# product_038.net
KiCad netlist of a schematic drawn in EAGLE
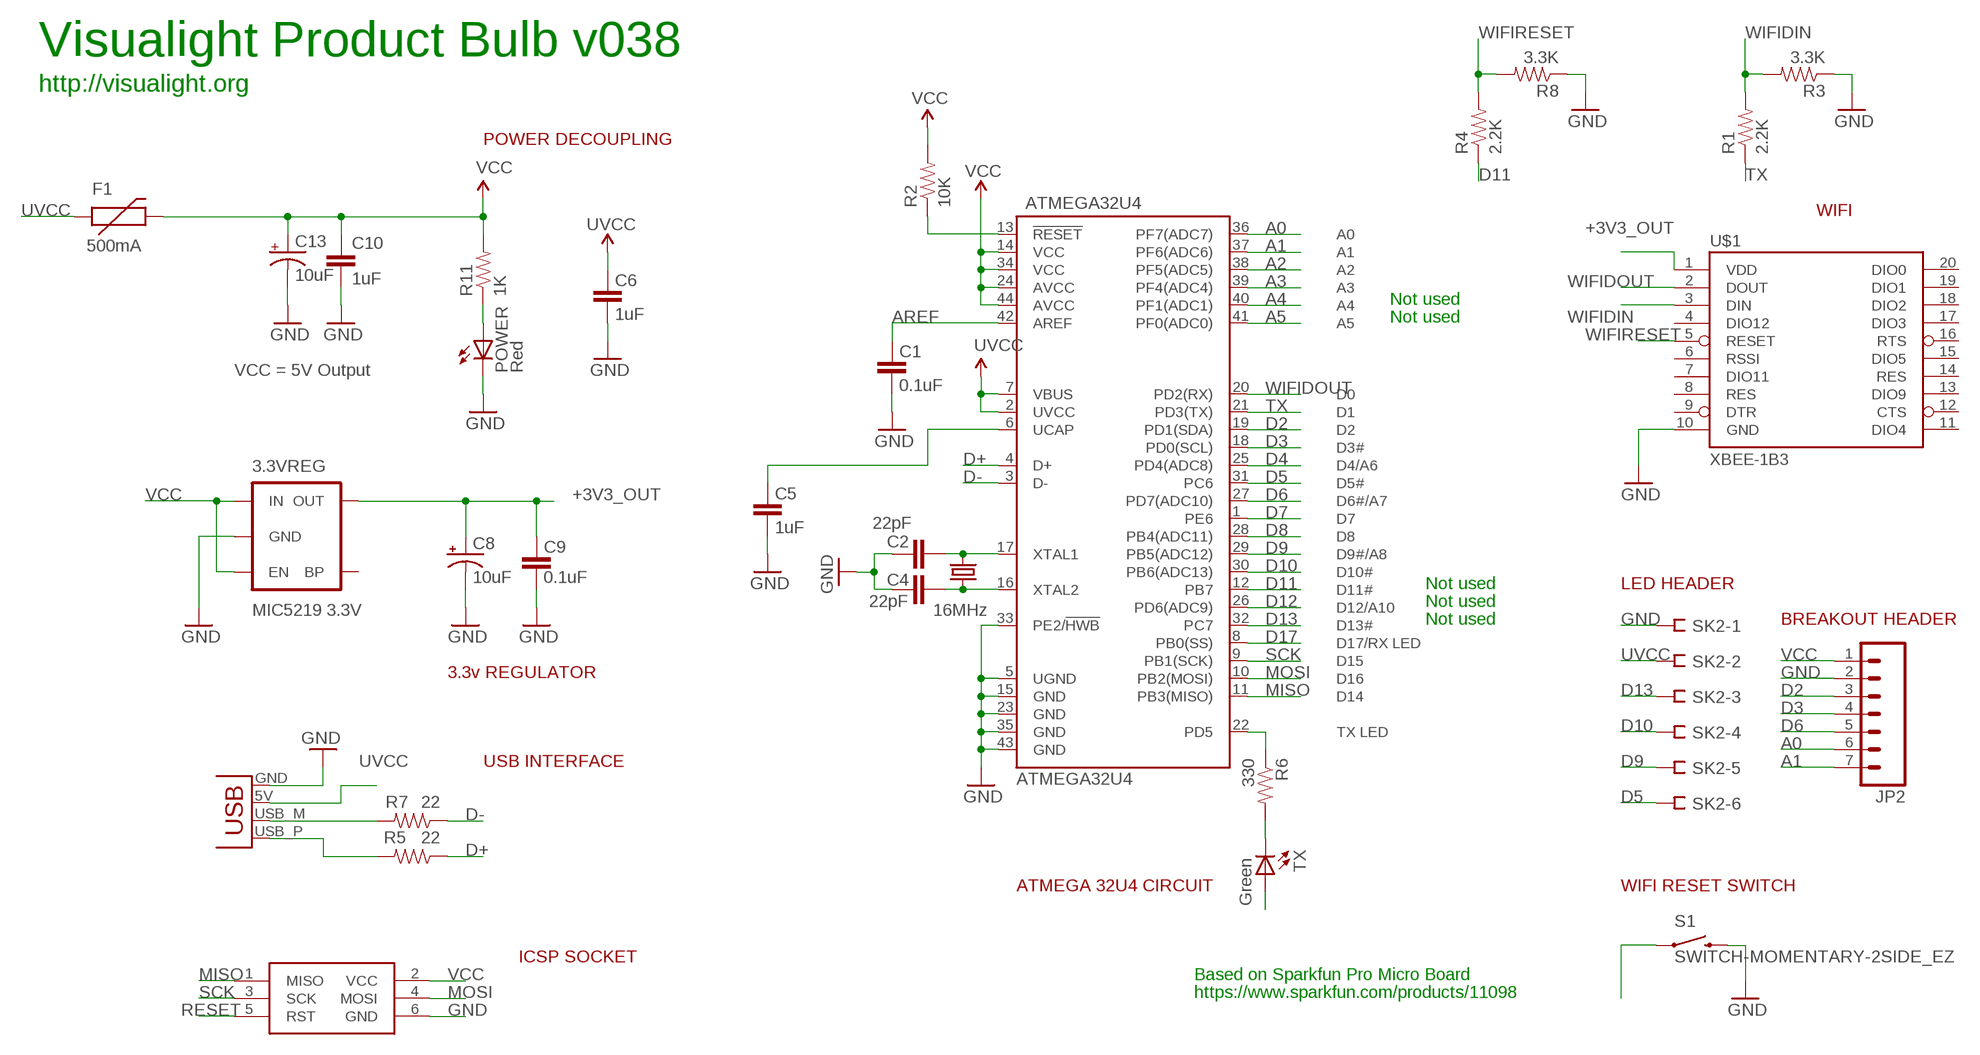
[diagram p0: schematic, sheet 1]

(export (version "E")
  (design (tool "Eeschema 10.0.6"))
  (components
    (comp (ref "3.3VREG")
      (value "MIC5219 3.3V")
      (footprint "eagle-import:SOT23-5")
      (libsource (lib "eagle-import") (part "V_REG_MIC52193.3V"))
    )
    (comp (ref "ATMEGA32U4")
      (value "ATMEGA32U4")
      (footprint "eagle-import:SPARKFUN-DIGITALIC_TQFP44")
      (libsource (lib "eagle-import") (part "ATMEGA32U4TQFP"))
    )
    (comp (ref "C1")
      (value "0.1uF")
      (footprint "eagle-import:0402-CAP")
      (libsource (lib "eagle-import") (part "CAP0402-CAP"))
    )
    (comp (ref "C2")
      (value "22pF")
      (footprint "eagle-import:0402-CAP")
      (libsource (lib "eagle-import") (part "CAP0402-CAP"))
    )
    (comp (ref "C4")
      (value "22pF")
      (footprint "eagle-import:0402-CAP")
      (libsource (lib "eagle-import") (part "CAP0402-CAP"))
    )
    (comp (ref "C5")
      (value "1uF")
      (footprint "eagle-import:0402-CAP")
      (libsource (lib "eagle-import") (part "CAP0402-CAP"))
    )
    (comp (ref "C6")
      (value "1uF")
      (footprint "eagle-import:0402-CAP")
      (libsource (lib "eagle-import") (part "CAP0402-CAP"))
    )
    (comp (ref "C8")
      (value "10uF")
      (footprint "eagle-import:EIA3216")
      (libsource (lib "eagle-import") (part "CAP_POL1206"))
    )
    (comp (ref "C9")
      (value "0.1uF")
      (footprint "eagle-import:0402-CAP")
      (libsource (lib "eagle-import") (part "CAP0402-CAP"))
    )
    (comp (ref "C10")
      (value "1uF")
      (footprint "eagle-import:0402-CAP")
      (libsource (lib "eagle-import") (part "CAP0402-CAP"))
    )
    (comp (ref "C13")
      (value "10uF")
      (footprint "eagle-import:EIA3216")
      (libsource (lib "eagle-import") (part "CAP_POL1206"))
    )
    (comp (ref "F1")
      (value "500mA")
      (footprint "eagle-import:PTC-1206")
      (libsource (lib "eagle-import") (part "PTCSMD"))
    )
    (comp (ref "ISP1")
      (value "AVRISP-6")
      (footprint "eagle-import:AVRISP")
      (libsource (lib "eagle-import") (part "AVRISP-6"))
    )
    (comp (ref "JP2")
      (value "M07")
      (footprint "eagle-import:1X07")
      (libsource (lib "eagle-import") (part "M07"))
    )
    (comp (ref "POWER")
      (value "Red")
      (footprint "eagle-import:LED-0603")
      (libsource (lib "eagle-import") (part "LED0603"))
    )
    (comp (ref "R1")
      (value "2.2K")
      (footprint "eagle-import:0402-RES")
      (libsource (lib "eagle-import") (part "RESISTOR0402-RES"))
    )
    (comp (ref "R2")
      (value "10K")
      (footprint "eagle-import:0402-RES")
      (libsource (lib "eagle-import") (part "RESISTOR0402-RES"))
    )
    (comp (ref "R3")
      (value "3.3K")
      (footprint "eagle-import:0402-RES")
      (libsource (lib "eagle-import") (part "RESISTOR0402-RES"))
    )
    (comp (ref "R4")
      (value "2.2K")
      (footprint "eagle-import:0402-RES")
      (libsource (lib "eagle-import") (part "RESISTOR0402-RES"))
    )
    (comp (ref "R5")
      (value "22")
      (footprint "eagle-import:0402-RES")
      (libsource (lib "eagle-import") (part "RESISTOR0402-RES"))
    )
    (comp (ref "R6")
      (value "330")
      (footprint "eagle-import:0402-RES")
      (libsource (lib "eagle-import") (part "RESISTOR0402-RES"))
    )
    (comp (ref "R7")
      (value "22")
      (footprint "eagle-import:0402-RES")
      (libsource (lib "eagle-import") (part "RESISTOR0402-RES"))
    )
    (comp (ref "R8")
      (value "3.3K")
      (footprint "eagle-import:0402-RES")
      (libsource (lib "eagle-import") (part "RESISTOR0402-RES"))
    )
    (comp (ref "R11")
      (value "1K")
      (footprint "eagle-import:0402-RES")
      (libsource (lib "eagle-import") (part "RESISTOR0402-RES"))
    )
    (comp (ref "S1")
      (value "SWITCH-MOMENTARY-2SIDE_EZ")
      (footprint "eagle-import:TACTILE-PTH-SIDEEZ")
      (libsource (lib "eagle-import") (part "SWITCH-MOMENTARY-2SIDE_EZ"))
    )
    (comp (ref "SK2")
      (value "DF3-06S")
      (footprint "eagle-import:DF3S-06")
      (libsource (lib "eagle-import") (part "DF3-06S"))
    )
    (comp (ref "TX")
      (value "Green")
      (footprint "eagle-import:LED-0603")
      (libsource (lib "eagle-import") (part "LED0603"))
    )
    (comp (ref "U$1")
      (value "XBEE-1B3")
      (footprint "eagle-import:XBEE-SMD")
      (libsource (lib "eagle-import") (part "XBEE-1B3"))
    )
    (comp (ref "X2")
      (value "USBPCB")
      (footprint "eagle-import:USB-A-PCB")
      (libsource (lib "eagle-import") (part "USBPCB"))
    )
    (comp (ref "Y1")
      (value "16MHz")
      (footprint "eagle-import:CRYSTAL-SMD-5X3")
      (libsource (lib "eagle-import") (part "CRYSTAL5X3"))
    )
  )
  (nets
    (net (code "1") (name "/+3V3_OUT") (class "Default")
      (node (ref "3.3VREG") (pin "5") (pinfunction "OUT_5") (pintype "passive"))
      (node (ref "C8") (pin "A") (pinfunction "+_A") (pintype "passive"))
      (node (ref "C9") (pin "2") (pinfunction "2_2") (pintype "passive"))
      (node (ref "U$1") (pin "1") (pinfunction "VDD_1") (pintype "power_in"))
    )
    (net (code "2") (name "/A0") (class "Default")
      (node (ref "ATMEGA32U4") (pin "36") (pinfunction "PF7(ADC7)_36") (pintype "bidirectional"))
      (node (ref "JP2") (pin "6") (pinfunction "6_6") (pintype "passive"))
    )
    (net (code "3") (name "/A1") (class "Default")
      (node (ref "ATMEGA32U4") (pin "37") (pinfunction "PF6(ADC6)_37") (pintype "bidirectional"))
      (node (ref "JP2") (pin "7") (pinfunction "7_7") (pintype "passive"))
    )
    (net (code "4") (name "/A2") (class "Default")
      (node (ref "ATMEGA32U4") (pin "38") (pinfunction "PF5(ADC5)_38") (pintype "bidirectional"))
    )
    (net (code "5") (name "/A3") (class "Default")
      (node (ref "ATMEGA32U4") (pin "39") (pinfunction "PF4(ADC4)_39") (pintype "bidirectional"))
    )
    (net (code "6") (name "/A4") (class "Default")
      (node (ref "ATMEGA32U4") (pin "40") (pinfunction "PF1(ADC1)_40") (pintype "bidirectional"))
    )
    (net (code "7") (name "/A5") (class "Default")
      (node (ref "ATMEGA32U4") (pin "41") (pinfunction "PF0(ADC0)_41") (pintype "bidirectional"))
    )
    (net (code "8") (name "/AREF") (class "Default")
      (node (ref "ATMEGA32U4") (pin "42") (pinfunction "AREF_42") (pintype "bidirectional"))
      (node (ref "C1") (pin "2") (pinfunction "2_2") (pintype "passive"))
    )
    (net (code "9") (name "/D+") (class "Default")
      (node (ref "ATMEGA32U4") (pin "4") (pinfunction "D+_4") (pintype "bidirectional"))
      (node (ref "R5") (pin "1") (pinfunction "1_1") (pintype "passive"))
    )
    (net (code "10") (name "/D-") (class "Default")
      (node (ref "ATMEGA32U4") (pin "3") (pinfunction "D-_3") (pintype "bidirectional"))
      (node (ref "R7") (pin "1") (pinfunction "1_1") (pintype "passive"))
    )
    (net (code "11") (name "/D2") (class "Default")
      (node (ref "ATMEGA32U4") (pin "19") (pinfunction "PD1(SDA)_19") (pintype "bidirectional"))
      (node (ref "JP2") (pin "3") (pinfunction "3_3") (pintype "passive"))
    )
    (net (code "12") (name "/D3") (class "Default")
      (node (ref "ATMEGA32U4") (pin "18") (pinfunction "PD0(SCL)_18") (pintype "bidirectional"))
      (node (ref "JP2") (pin "4") (pinfunction "4_4") (pintype "passive"))
    )
    (net (code "13") (name "/D4") (class "Default")
      (node (ref "ATMEGA32U4") (pin "25") (pinfunction "PD4(ADC8)_25") (pintype "bidirectional"))
    )
    (net (code "14") (name "/D5") (class "Default")
      (node (ref "ATMEGA32U4") (pin "31") (pinfunction "PC6_31") (pintype "bidirectional"))
      (node (ref "SK2") (pin "6") (pinfunction "S_6") (pintype "passive"))
    )
    (net (code "15") (name "/D6") (class "Default")
      (node (ref "ATMEGA32U4") (pin "27") (pinfunction "PD7(ADC10)_27") (pintype "bidirectional"))
      (node (ref "JP2") (pin "5") (pinfunction "5_5") (pintype "passive"))
    )
    (net (code "16") (name "/D7") (class "Default")
      (node (ref "ATMEGA32U4") (pin "1") (pinfunction "PE6_1") (pintype "bidirectional"))
      (node (ref "S1") (pin "1") (pinfunction "1_1") (pintype "passive"))
    )
    (net (code "17") (name "/D8") (class "Default")
      (node (ref "ATMEGA32U4") (pin "28") (pinfunction "PB4(ADC11)_28") (pintype "bidirectional"))
    )
    (net (code "18") (name "/D9") (class "Default")
      (node (ref "ATMEGA32U4") (pin "29") (pinfunction "PB5(ADC12)_29") (pintype "bidirectional"))
      (node (ref "SK2") (pin "5") (pinfunction "S_5") (pintype "passive"))
    )
    (net (code "19") (name "/D10") (class "Default")
      (node (ref "ATMEGA32U4") (pin "30") (pinfunction "PB6(ADC13)_30") (pintype "bidirectional"))
      (node (ref "SK2") (pin "4") (pinfunction "S_4") (pintype "passive"))
    )
    (net (code "20") (name "/D11") (class "Default")
      (node (ref "ATMEGA32U4") (pin "12") (pinfunction "PB7_12") (pintype "bidirectional"))
      (node (ref "R4") (pin "1") (pinfunction "1_1") (pintype "passive"))
    )
    (net (code "21") (name "/D12") (class "Default")
      (node (ref "ATMEGA32U4") (pin "26") (pinfunction "PD6(ADC9)_26") (pintype "bidirectional"))
    )
    (net (code "22") (name "/D13") (class "Default")
      (node (ref "ATMEGA32U4") (pin "32") (pinfunction "PC7_32") (pintype "bidirectional"))
      (node (ref "SK2") (pin "3") (pinfunction "S_3") (pintype "passive"))
    )
    (net (code "23") (name "/D17") (class "Default")
      (node (ref "ATMEGA32U4") (pin "8") (pinfunction "PB0(SS)_8") (pintype "bidirectional"))
    )
    (net (code "24") (name "/MISO") (class "Default")
      (node (ref "ATMEGA32U4") (pin "11") (pinfunction "PB3(MISO)_11") (pintype "bidirectional"))
      (node (ref "ISP1") (pin "1") (pinfunction "MISO_1") (pintype "input"))
    )
    (net (code "25") (name "/MOSI") (class "Default")
      (node (ref "ATMEGA32U4") (pin "10") (pinfunction "PB2(MOSI)_10") (pintype "bidirectional"))
      (node (ref "ISP1") (pin "4") (pinfunction "MOSI_4") (pintype "output"))
    )
    (net (code "26") (name "/RESET") (class "Default")
      (node (ref "ATMEGA32U4") (pin "13") (pinfunction "~{RESET}_13") (pintype "bidirectional"))
      (node (ref "ISP1") (pin "5") (pinfunction "RST_5") (pintype "output"))
      (node (ref "R2") (pin "1") (pinfunction "1_1") (pintype "passive"))
    )
    (net (code "27") (name "/SCK") (class "Default")
      (node (ref "ATMEGA32U4") (pin "9") (pinfunction "PB1(SCK)_9") (pintype "bidirectional"))
      (node (ref "ISP1") (pin "3") (pinfunction "SCK_3") (pintype "output"))
    )
    (net (code "28") (name "/TX") (class "Default")
      (node (ref "ATMEGA32U4") (pin "21") (pinfunction "PD3(TX)_21") (pintype "bidirectional"))
      (node (ref "R1") (pin "1") (pinfunction "1_1") (pintype "passive"))
    )
    (net (code "29") (name "/WIFIDIN") (class "Default")
      (node (ref "R1") (pin "2") (pinfunction "2_2") (pintype "passive"))
      (node (ref "R3") (pin "2") (pinfunction "2_2") (pintype "passive"))
      (node (ref "U$1") (pin "3") (pinfunction "DIN_3") (pintype "input"))
    )
    (net (code "30") (name "/WIFIDOUT") (class "Default")
      (node (ref "ATMEGA32U4") (pin "20") (pinfunction "PD2(RX)_20") (pintype "bidirectional"))
      (node (ref "U$1") (pin "2") (pinfunction "DOUT_2") (pintype "output"))
    )
    (net (code "31") (name "/WIFIRESET") (class "Default")
      (node (ref "R4") (pin "2") (pinfunction "2_2") (pintype "passive"))
      (node (ref "R8") (pin "2") (pinfunction "2_2") (pintype "passive"))
      (node (ref "U$1") (pin "5") (pinfunction "RESET_5") (pintype "input"))
    )
    (net (code "32") (name "GND") (class "Default")
      (node (ref "3.3VREG") (pin "2") (pinfunction "GND_2") (pintype "input"))
      (node (ref "ATMEGA32U4") (pin "15") (pinfunction "GND_15") (pintype "bidirectional"))
      (node (ref "ATMEGA32U4") (pin "23") (pinfunction "GND_23") (pintype "bidirectional"))
      (node (ref "ATMEGA32U4") (pin "33") (pinfunction "PE2/~{HWB}_33") (pintype "bidirectional"))
      (node (ref "ATMEGA32U4") (pin "35") (pinfunction "GND_35") (pintype "bidirectional"))
      (node (ref "ATMEGA32U4") (pin "43") (pinfunction "GND_43") (pintype "bidirectional"))
      (node (ref "ATMEGA32U4") (pin "5") (pinfunction "UGND_5") (pintype "bidirectional"))
      (node (ref "C1") (pin "1") (pinfunction "1_1") (pintype "passive"))
      (node (ref "C10") (pin "2") (pinfunction "2_2") (pintype "passive"))
      (node (ref "C13") (pin "C") (pinfunction "-_C") (pintype "passive"))
      (node (ref "C2") (pin "2") (pinfunction "2_2") (pintype "passive"))
      (node (ref "C4") (pin "2") (pinfunction "2_2") (pintype "passive"))
      (node (ref "C5") (pin "1") (pinfunction "1_1") (pintype "passive"))
      (node (ref "C6") (pin "1") (pinfunction "1_1") (pintype "passive"))
      (node (ref "C8") (pin "C") (pinfunction "-_C") (pintype "passive"))
      (node (ref "C9") (pin "1") (pinfunction "1_1") (pintype "passive"))
      (node (ref "ISP1") (pin "6") (pinfunction "GND_6") (pintype "power_in"))
      (node (ref "JP2") (pin "2") (pinfunction "2_2") (pintype "passive"))
      (node (ref "POWER") (pin "C") (pinfunction "C_C") (pintype "passive"))
      (node (ref "R3") (pin "1") (pinfunction "1_1") (pintype "passive"))
      (node (ref "R8") (pin "1") (pinfunction "1_1") (pintype "passive"))
      (node (ref "S1") (pin "2") (pinfunction "2_2") (pintype "passive"))
      (node (ref "SK2") (pin "1") (pinfunction "S_1") (pintype "passive"))
      (node (ref "U$1") (pin "10") (pinfunction "GND_10") (pintype "power_in"))
      (node (ref "X2") (pin "GND") (pinfunction "GND_GND") (pintype "bidirectional"))
    )
    (net (code "33") (name "Net-(ATMEGA32U4-PD5)") (class "Default")
      (node (ref "ATMEGA32U4") (pin "22") (pinfunction "PD5_22") (pintype "bidirectional"))
      (node (ref "R6") (pin "1") (pinfunction "1_1") (pintype "passive"))
    )
    (net (code "34") (name "Net-(ATMEGA32U4-UCAP)") (class "Default")
      (node (ref "ATMEGA32U4") (pin "6") (pinfunction "UCAP_6") (pintype "bidirectional"))
      (node (ref "C5") (pin "2") (pinfunction "2_2") (pintype "passive"))
    )
    (net (code "35") (name "Net-(ATMEGA32U4-XTAL1)") (class "Default")
      (node (ref "ATMEGA32U4") (pin "17") (pinfunction "XTAL1_17") (pintype "bidirectional"))
      (node (ref "C2") (pin "1") (pinfunction "1_1") (pintype "passive"))
      (node (ref "Y1") (pin "3") (pinfunction "2_3") (pintype "passive"))
    )
    (net (code "36") (name "Net-(ATMEGA32U4-XTAL2)") (class "Default")
      (node (ref "ATMEGA32U4") (pin "16") (pinfunction "XTAL2_16") (pintype "bidirectional"))
      (node (ref "C4") (pin "1") (pinfunction "1_1") (pintype "passive"))
      (node (ref "Y1") (pin "1") (pinfunction "1_1") (pintype "passive"))
    )
    (net (code "37") (name "Net-(POWER-PadA)") (class "Default")
      (node (ref "POWER") (pin "A") (pinfunction "A_A") (pintype "passive"))
      (node (ref "R11") (pin "1") (pinfunction "1_1") (pintype "passive"))
    )
    (net (code "38") (name "Net-(R6-Pad2)") (class "Default")
      (node (ref "R6") (pin "2") (pinfunction "2_2") (pintype "passive"))
      (node (ref "TX") (pin "C") (pinfunction "C_C") (pintype "passive"))
    )
    (net (code "39") (name "Net-(X2-D+)") (class "Default")
      (node (ref "R5") (pin "2") (pinfunction "2_2") (pintype "passive"))
      (node (ref "X2") (pin "USB_P") (pinfunction "D+_USB_P") (pintype "bidirectional"))
    )
    (net (code "40") (name "Net-(X2-D-)") (class "Default")
      (node (ref "R7") (pin "2") (pinfunction "2_2") (pintype "passive"))
      (node (ref "X2") (pin "USB_M") (pinfunction "D-_USB_M") (pintype "bidirectional"))
    )
    (net (code "41") (name "UVCC") (class "Default")
      (node (ref "ATMEGA32U4") (pin "2") (pinfunction "UVCC_2") (pintype "bidirectional"))
      (node (ref "ATMEGA32U4") (pin "7") (pinfunction "VBUS_7") (pintype "bidirectional"))
      (node (ref "C6") (pin "2") (pinfunction "2_2") (pintype "passive"))
      (node (ref "F1") (pin "1") (pinfunction "1_1") (pintype "bidirectional"))
      (node (ref "SK2") (pin "2") (pinfunction "S_2") (pintype "passive"))
      (node (ref "X2") (pin "5V") (pinfunction "VBUS_5V") (pintype "bidirectional"))
    )
    (net (code "42") (name "VCC") (class "Default")
      (node (ref "3.3VREG") (pin "1") (pinfunction "IN_1") (pintype "input"))
      (node (ref "3.3VREG") (pin "3") (pinfunction "EN_3") (pintype "input"))
      (node (ref "ATMEGA32U4") (pin "14") (pinfunction "VCC_14") (pintype "bidirectional"))
      (node (ref "ATMEGA32U4") (pin "24") (pinfunction "AVCC_24") (pintype "bidirectional"))
      (node (ref "ATMEGA32U4") (pin "34") (pinfunction "VCC_34") (pintype "bidirectional"))
      (node (ref "ATMEGA32U4") (pin "44") (pinfunction "AVCC_44") (pintype "bidirectional"))
      (node (ref "C10") (pin "1") (pinfunction "1_1") (pintype "passive"))
      (node (ref "C13") (pin "A") (pinfunction "+_A") (pintype "passive"))
      (node (ref "F1") (pin "2") (pinfunction "2_2") (pintype "bidirectional"))
      (node (ref "ISP1") (pin "2") (pinfunction "VCC_2") (pintype "power_in"))
      (node (ref "JP2") (pin "1") (pinfunction "1_1") (pintype "passive"))
      (node (ref "R11") (pin "2") (pinfunction "2_2") (pintype "passive"))
      (node (ref "R2") (pin "2") (pinfunction "2_2") (pintype "passive"))
      (node (ref "TX") (pin "A") (pinfunction "A_A") (pintype "passive"))
    )
    (net (code "43") (name "unconnected-(3.3VREG-BP-Pad4)") (class "Default")
      (node (ref "3.3VREG") (pin "4") (pinfunction "BP_4") (pintype "input"))
    )
    (net (code "44") (name "unconnected-(U$1-CTS-Pad12)") (class "Default")
      (node (ref "U$1") (pin "12") (pinfunction "CTS_12") (pintype "output"))
    )
    (net (code "45") (name "unconnected-(U$1-DIO0-Pad20)") (class "Default")
      (node (ref "U$1") (pin "20") (pinfunction "DIO0_20") (pintype "bidirectional"))
    )
    (net (code "46") (name "unconnected-(U$1-DIO1-Pad19)") (class "Default")
      (node (ref "U$1") (pin "19") (pinfunction "DIO1_19") (pintype "bidirectional"))
    )
    (net (code "47") (name "unconnected-(U$1-DIO2-Pad18)") (class "Default")
      (node (ref "U$1") (pin "18") (pinfunction "DIO2_18") (pintype "bidirectional"))
    )
    (net (code "48") (name "unconnected-(U$1-DIO3-Pad17)") (class "Default")
      (node (ref "U$1") (pin "17") (pinfunction "DIO3_17") (pintype "bidirectional"))
    )
    (net (code "49") (name "unconnected-(U$1-DIO4-Pad11)") (class "Default")
      (node (ref "U$1") (pin "11") (pinfunction "DIO4_11") (pintype "bidirectional"))
    )
    (net (code "50") (name "unconnected-(U$1-DIO5-Pad15)") (class "Default")
      (node (ref "U$1") (pin "15") (pinfunction "DIO5_15") (pintype "bidirectional"))
    )
    (net (code "51") (name "unconnected-(U$1-DIO9-Pad13)") (class "Default")
      (node (ref "U$1") (pin "13") (pinfunction "DIO9_13") (pintype "bidirectional"))
    )
    (net (code "52") (name "unconnected-(U$1-DIO11-Pad7)") (class "Default")
      (node (ref "U$1") (pin "7") (pinfunction "DIO11_7") (pintype "bidirectional"))
    )
    (net (code "53") (name "unconnected-(U$1-DIO12-Pad4)") (class "Default")
      (node (ref "U$1") (pin "4") (pinfunction "DIO12_4") (pintype "bidirectional"))
    )
    (net (code "54") (name "unconnected-(U$1-DTR-Pad9)") (class "Default")
      (node (ref "U$1") (pin "9") (pinfunction "DTR_9") (pintype "bidirectional"))
    )
    (net (code "55") (name "unconnected-(U$1-RES-Pad8)") (class "Default")
      (node (ref "U$1") (pin "8") (pinfunction "RES_8") (pintype "bidirectional"))
    )
    (net (code "56") (name "unconnected-(U$1-RES-Pad14)") (class "Default")
      (node (ref "U$1") (pin "14") (pinfunction "RES_14") (pintype "bidirectional"))
    )
    (net (code "57") (name "unconnected-(U$1-RSSI-Pad6)") (class "Default")
      (node (ref "U$1") (pin "6") (pinfunction "RSSI_6") (pintype "bidirectional"))
    )
    (net (code "58") (name "unconnected-(U$1-RTS-Pad16)") (class "Default")
      (node (ref "U$1") (pin "16") (pinfunction "RTS_16") (pintype "input"))
    )
  )
)
